# RGB_LEDs.net
KiCad netlist of a schematic drawn in Altium Designer
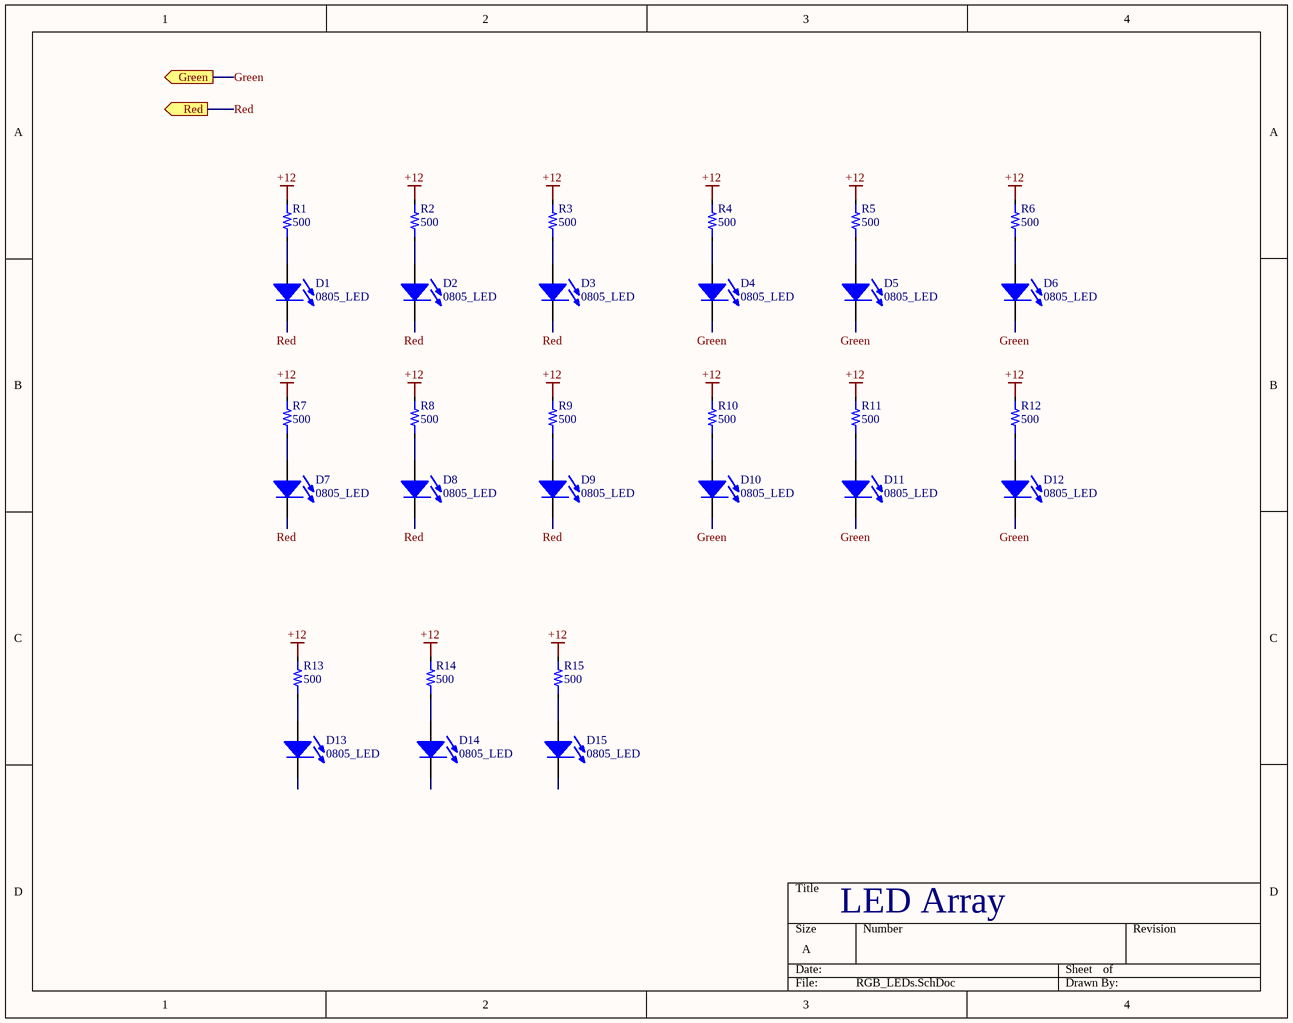
[diagram p0: RGB_LEDs.SchDoc]

(export (version "E")
  (design (tool "Eeschema 10.0.6"))
  (components
    (comp (ref "D1")
      (value "0805_LED")
      (footprint "0805_LED")
      (description "Generic 0805 LED")
      (libsource (lib "Diodes") (part "0805_LED"))
    )
    (comp (ref "D2")
      (value "0805_LED")
      (footprint "0805_LED")
      (description "Generic 0805 LED")
      (libsource (lib "Diodes") (part "0805_LED"))
    )
    (comp (ref "D3")
      (value "0805_LED")
      (footprint "0805_LED")
      (description "Generic 0805 LED")
      (libsource (lib "Diodes") (part "0805_LED"))
    )
    (comp (ref "D4")
      (value "0805_LED")
      (footprint "0805_LED")
      (description "Generic 0805 LED")
      (libsource (lib "Diodes") (part "0805_LED"))
    )
    (comp (ref "D5")
      (value "0805_LED")
      (footprint "0805_LED")
      (description "Generic 0805 LED")
      (libsource (lib "Diodes") (part "0805_LED"))
    )
    (comp (ref "D6")
      (value "0805_LED")
      (footprint "0805_LED")
      (description "Generic 0805 LED")
      (libsource (lib "Diodes") (part "0805_LED"))
    )
    (comp (ref "D7")
      (value "0805_LED")
      (footprint "0805_LED")
      (description "Generic 0805 LED")
      (libsource (lib "Diodes") (part "0805_LED"))
    )
    (comp (ref "D8")
      (value "0805_LED")
      (footprint "0805_LED")
      (description "Generic 0805 LED")
      (libsource (lib "Diodes") (part "0805_LED"))
    )
    (comp (ref "D9")
      (value "0805_LED")
      (footprint "0805_LED")
      (description "Generic 0805 LED")
      (libsource (lib "Diodes") (part "0805_LED"))
    )
    (comp (ref "D10")
      (value "0805_LED")
      (footprint "0805_LED")
      (description "Generic 0805 LED")
      (libsource (lib "Diodes") (part "0805_LED"))
    )
    (comp (ref "D11")
      (value "0805_LED")
      (footprint "0805_LED")
      (description "Generic 0805 LED")
      (libsource (lib "Diodes") (part "0805_LED"))
    )
    (comp (ref "D12")
      (value "0805_LED")
      (footprint "0805_LED")
      (description "Generic 0805 LED")
      (libsource (lib "Diodes") (part "0805_LED"))
    )
    (comp (ref "D13")
      (value "0805_LED")
      (footprint "0805_LED")
      (description "Generic 0805 LED")
      (libsource (lib "Diodes") (part "0805_LED"))
    )
    (comp (ref "D14")
      (value "0805_LED")
      (footprint "0805_LED")
      (description "Generic 0805 LED")
      (libsource (lib "Diodes") (part "0805_LED"))
    )
    (comp (ref "D15")
      (value "0805_LED")
      (footprint "0805_LED")
      (description "Generic 0805 LED")
      (libsource (lib "Diodes") (part "0805_LED"))
    )
    (comp (ref "R1")
      (value "500")
      (footprint "0603_RES")
      (fields (field (name "Comment") "Resistor"))
      (libsource (lib "Resistors") (part "Resistor"))
    )
    (comp (ref "R2")
      (value "500")
      (footprint "0603_RES")
      (fields (field (name "Comment") "Resistor"))
      (libsource (lib "Resistors") (part "Resistor"))
    )
    (comp (ref "R3")
      (value "500")
      (footprint "0603_RES")
      (fields (field (name "Comment") "Resistor"))
      (libsource (lib "Resistors") (part "Resistor"))
    )
    (comp (ref "R4")
      (value "500")
      (footprint "0603_RES")
      (fields (field (name "Comment") "Resistor"))
      (libsource (lib "Resistors") (part "Resistor"))
    )
    (comp (ref "R5")
      (value "500")
      (footprint "0603_RES")
      (fields (field (name "Comment") "Resistor"))
      (libsource (lib "Resistors") (part "Resistor"))
    )
    (comp (ref "R6")
      (value "500")
      (footprint "0603_RES")
      (fields (field (name "Comment") "Resistor"))
      (libsource (lib "Resistors") (part "Resistor"))
    )
    (comp (ref "R7")
      (value "500")
      (footprint "0603_RES")
      (fields (field (name "Comment") "Resistor"))
      (libsource (lib "Resistors") (part "Resistor"))
    )
    (comp (ref "R8")
      (value "500")
      (footprint "0603_RES")
      (fields (field (name "Comment") "Resistor"))
      (libsource (lib "Resistors") (part "Resistor"))
    )
    (comp (ref "R9")
      (value "500")
      (footprint "0603_RES")
      (fields (field (name "Comment") "Resistor"))
      (libsource (lib "Resistors") (part "Resistor"))
    )
    (comp (ref "R10")
      (value "500")
      (footprint "0603_RES")
      (fields (field (name "Comment") "Resistor"))
      (libsource (lib "Resistors") (part "Resistor"))
    )
    (comp (ref "R11")
      (value "500")
      (footprint "0603_RES")
      (fields (field (name "Comment") "Resistor"))
      (libsource (lib "Resistors") (part "Resistor"))
    )
    (comp (ref "R12")
      (value "500")
      (footprint "0603_RES")
      (fields (field (name "Comment") "Resistor"))
      (libsource (lib "Resistors") (part "Resistor"))
    )
    (comp (ref "R13")
      (value "500")
      (footprint "0603_RES")
      (fields (field (name "Comment") "Resistor"))
      (libsource (lib "Resistors") (part "Resistor"))
    )
    (comp (ref "R14")
      (value "500")
      (footprint "0603_RES")
      (fields (field (name "Comment") "Resistor"))
      (libsource (lib "Resistors") (part "Resistor"))
    )
    (comp (ref "R15")
      (value "500")
      (footprint "0603_RES")
      (fields (field (name "Comment") "Resistor"))
      (libsource (lib "Resistors") (part "Resistor"))
    )
  )
  (nets
    (net (code "1") (name "+12") (class "Default")
      (node (ref "R1") (pin "2") (pinfunction "2_2") (pintype "passive"))
      (node (ref "R10") (pin "2") (pinfunction "2_2") (pintype "passive"))
      (node (ref "R11") (pin "2") (pinfunction "2_2") (pintype "passive"))
      (node (ref "R12") (pin "2") (pinfunction "2_2") (pintype "passive"))
      (node (ref "R13") (pin "2") (pinfunction "2_2") (pintype "passive"))
      (node (ref "R14") (pin "2") (pinfunction "2_2") (pintype "passive"))
      (node (ref "R15") (pin "2") (pinfunction "2_2") (pintype "passive"))
      (node (ref "R2") (pin "2") (pinfunction "2_2") (pintype "passive"))
      (node (ref "R3") (pin "2") (pinfunction "2_2") (pintype "passive"))
      (node (ref "R4") (pin "2") (pinfunction "2_2") (pintype "passive"))
      (node (ref "R5") (pin "2") (pinfunction "2_2") (pintype "passive"))
      (node (ref "R6") (pin "2") (pinfunction "2_2") (pintype "passive"))
      (node (ref "R7") (pin "2") (pinfunction "2_2") (pintype "passive"))
      (node (ref "R8") (pin "2") (pinfunction "2_2") (pintype "passive"))
      (node (ref "R9") (pin "2") (pinfunction "2_2") (pintype "passive"))
    )
    (net (code "2") (name "/Green") (class "Default")
      (node (ref "D10") (pin "2") (pinfunction "K_2") (pintype "passive"))
      (node (ref "D11") (pin "2") (pinfunction "K_2") (pintype "passive"))
      (node (ref "D12") (pin "2") (pinfunction "K_2") (pintype "passive"))
      (node (ref "D4") (pin "2") (pinfunction "K_2") (pintype "passive"))
      (node (ref "D5") (pin "2") (pinfunction "K_2") (pintype "passive"))
      (node (ref "D6") (pin "2") (pinfunction "K_2") (pintype "passive"))
    )
    (net (code "3") (name "/Red") (class "Default")
      (node (ref "D1") (pin "2") (pinfunction "K_2") (pintype "passive"))
      (node (ref "D2") (pin "2") (pinfunction "K_2") (pintype "passive"))
      (node (ref "D3") (pin "2") (pinfunction "K_2") (pintype "passive"))
      (node (ref "D7") (pin "2") (pinfunction "K_2") (pintype "passive"))
      (node (ref "D8") (pin "2") (pinfunction "K_2") (pintype "passive"))
      (node (ref "D9") (pin "2") (pinfunction "K_2") (pintype "passive"))
    )
    (net (code "4") (name "Net-(D1-A)") (class "Default")
      (node (ref "D1") (pin "1") (pinfunction "A_1") (pintype "passive"))
      (node (ref "R1") (pin "1") (pinfunction "1_1") (pintype "passive"))
    )
    (net (code "5") (name "Net-(D2-A)") (class "Default")
      (node (ref "D2") (pin "1") (pinfunction "A_1") (pintype "passive"))
      (node (ref "R2") (pin "1") (pinfunction "1_1") (pintype "passive"))
    )
    (net (code "6") (name "Net-(D3-A)") (class "Default")
      (node (ref "D3") (pin "1") (pinfunction "A_1") (pintype "passive"))
      (node (ref "R3") (pin "1") (pinfunction "1_1") (pintype "passive"))
    )
    (net (code "7") (name "Net-(D4-A)") (class "Default")
      (node (ref "D4") (pin "1") (pinfunction "A_1") (pintype "passive"))
      (node (ref "R4") (pin "1") (pinfunction "1_1") (pintype "passive"))
    )
    (net (code "8") (name "Net-(D5-A)") (class "Default")
      (node (ref "D5") (pin "1") (pinfunction "A_1") (pintype "passive"))
      (node (ref "R5") (pin "1") (pinfunction "1_1") (pintype "passive"))
    )
    (net (code "9") (name "Net-(D6-A)") (class "Default")
      (node (ref "D6") (pin "1") (pinfunction "A_1") (pintype "passive"))
      (node (ref "R6") (pin "1") (pinfunction "1_1") (pintype "passive"))
    )
    (net (code "10") (name "Net-(D7-A)") (class "Default")
      (node (ref "D7") (pin "1") (pinfunction "A_1") (pintype "passive"))
      (node (ref "R7") (pin "1") (pinfunction "1_1") (pintype "passive"))
    )
    (net (code "11") (name "Net-(D8-A)") (class "Default")
      (node (ref "D8") (pin "1") (pinfunction "A_1") (pintype "passive"))
      (node (ref "R8") (pin "1") (pinfunction "1_1") (pintype "passive"))
    )
    (net (code "12") (name "Net-(D9-A)") (class "Default")
      (node (ref "D9") (pin "1") (pinfunction "A_1") (pintype "passive"))
      (node (ref "R9") (pin "1") (pinfunction "1_1") (pintype "passive"))
    )
    (net (code "13") (name "Net-(D10-A)") (class "Default")
      (node (ref "D10") (pin "1") (pinfunction "A_1") (pintype "passive"))
      (node (ref "R10") (pin "1") (pinfunction "1_1") (pintype "passive"))
    )
    (net (code "14") (name "Net-(D11-A)") (class "Default")
      (node (ref "D11") (pin "1") (pinfunction "A_1") (pintype "passive"))
      (node (ref "R11") (pin "1") (pinfunction "1_1") (pintype "passive"))
    )
    (net (code "15") (name "Net-(D12-A)") (class "Default")
      (node (ref "D12") (pin "1") (pinfunction "A_1") (pintype "passive"))
      (node (ref "R12") (pin "1") (pinfunction "1_1") (pintype "passive"))
    )
    (net (code "16") (name "Net-(D13-A)") (class "Default")
      (node (ref "D13") (pin "1") (pinfunction "A_1") (pintype "passive"))
      (node (ref "R13") (pin "1") (pinfunction "1_1") (pintype "passive"))
    )
    (net (code "17") (name "Net-(D14-A)") (class "Default")
      (node (ref "D14") (pin "1") (pinfunction "A_1") (pintype "passive"))
      (node (ref "R14") (pin "1") (pinfunction "1_1") (pintype "passive"))
    )
    (net (code "18") (name "Net-(D15-A)") (class "Default")
      (node (ref "D15") (pin "1") (pinfunction "A_1") (pintype "passive"))
      (node (ref "R15") (pin "1") (pinfunction "1_1") (pintype "passive"))
    )
    (net (code "19") (name "unconnected-(D13-K-Pad2)") (class "Default")
      (node (ref "D13") (pin "2") (pinfunction "K_2") (pintype "passive"))
    )
    (net (code "20") (name "unconnected-(D14-K-Pad2)") (class "Default")
      (node (ref "D14") (pin "2") (pinfunction "K_2") (pintype "passive"))
    )
    (net (code "21") (name "unconnected-(D15-K-Pad2)") (class "Default")
      (node (ref "D15") (pin "2") (pinfunction "K_2") (pintype "passive"))
    )
  )
)
